# AMP_2_0_Single_Channel.net
KiCad netlist of a schematic drawn in EAGLE
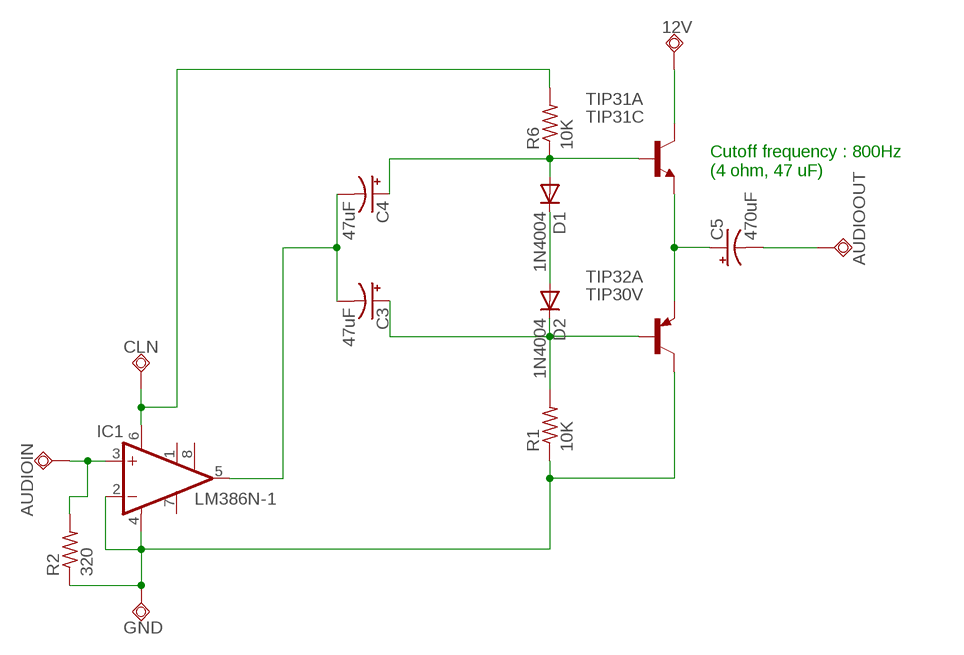
[diagram p0: schematic, sheet 1]

(export (version "E")
  (design (tool "Eeschema 10.0.6"))
  (components
    (comp (ref "12V")
      (value "TPSQPAD1-20")
      (footprint "eagle-import:P1-20")
      (libsource (lib "eagle-import") (part "TPSQPAD1-20"))
    )
    (comp (ref "AUDIOIN")
      (value "TPSQPAD1-20")
      (footprint "eagle-import:P1-20")
      (libsource (lib "eagle-import") (part "TPSQPAD1-20"))
    )
    (comp (ref "AUDIOOUT")
      (value "TPSQPAD1-20")
      (footprint "eagle-import:P1-20")
      (libsource (lib "eagle-import") (part "TPSQPAD1-20"))
    )
    (comp (ref "C3")
      (value "47uF")
      (footprint "eagle-import:E5-4")
      (libsource (lib "eagle-import") (part "CPOL-USE5-4"))
    )
    (comp (ref "C4")
      (value "47uF")
      (footprint "eagle-import:E5-4")
      (libsource (lib "eagle-import") (part "CPOL-USE5-4"))
    )
    (comp (ref "C5")
      (value "470uF")
      (footprint "eagle-import:E5-4")
      (libsource (lib "eagle-import") (part "CPOL-USE5-4"))
    )
    (comp (ref "CLN")
      (value "TPSQPAD1-20")
      (footprint "eagle-import:P1-20")
      (libsource (lib "eagle-import") (part "TPSQPAD1-20"))
    )
    (comp (ref "D1")
      (value "1N4004")
      (footprint "eagle-import:DO41-10")
      (libsource (lib "eagle-import") (part "1N4004"))
    )
    (comp (ref "D2")
      (value "1N4004")
      (footprint "eagle-import:DO41-10")
      (libsource (lib "eagle-import") (part "1N4004"))
    )
    (comp (ref "GND")
      (value "TPSQPAD1-20")
      (footprint "eagle-import:P1-20")
      (libsource (lib "eagle-import") (part "TPSQPAD1-20"))
    )
    (comp (ref "IC1")
      (value "LM386N-1")
      (footprint "eagle-import:DIL08")
      (libsource (lib "eagle-import") (part "LM386?-N1"))
    )
    (comp (ref "R1")
      (value "10K")
      (footprint "eagle-import:0204_7")
      (libsource (lib "eagle-import") (part "R-US_0204/7"))
    )
    (comp (ref "R2")
      (value "320")
      (footprint "eagle-import:0204_7")
      (libsource (lib "eagle-import") (part "R-US_0204/7"))
    )
    (comp (ref "R6")
      (value "10K")
      (footprint "eagle-import:0204_7")
      (libsource (lib "eagle-import") (part "R-US_0204/7"))
    )
    (comp (ref "TIP31A")
      (value "TIP31C")
      (footprint "eagle-import:TO220V")
      (libsource (lib "eagle-import") (part "TIP31C"))
    )
    (comp (ref "TIP32A")
      (value "TIP30V")
      (footprint "eagle-import:TO220V")
      (libsource (lib "eagle-import") (part "TIP30V"))
    )
  )
  (nets
    (net (code "1") (name "Net-(AUDIOOUT-PadTP)") (class "Default")
      (node (ref "AUDIOOUT") (pin "TP") (pinfunction "TP_TP") (pintype "input"))
      (node (ref "C5") (pin "-") (pinfunction "-_-") (pintype "passive"))
    )
    (net (code "2") (name "Net-(D1-PadC)") (class "Default")
      (node (ref "D1") (pin "C") (pinfunction "C_C") (pintype "passive"))
      (node (ref "D2") (pin "A") (pinfunction "A_A") (pintype "passive"))
    )
    (net (code "3") (name "Net-(IC1-+IN)") (class "Default")
      (node (ref "AUDIOIN") (pin "TP") (pinfunction "TP_TP") (pintype "input"))
      (node (ref "IC1") (pin "3") (pinfunction "+IN_3") (pintype "input"))
      (node (ref "R2") (pin "2") (pinfunction "2_2") (pintype "passive"))
    )
    (net (code "4") (name "Net-(IC1--IN)") (class "Default")
      (node (ref "GND") (pin "TP") (pinfunction "TP_TP") (pintype "input"))
      (node (ref "IC1") (pin "2") (pinfunction "-IN_2") (pintype "input"))
      (node (ref "IC1") (pin "4") (pinfunction "GND_4") (pintype "power_in"))
      (node (ref "R1") (pin "1") (pinfunction "1_1") (pintype "passive"))
      (node (ref "R2") (pin "1") (pinfunction "1_1") (pintype "passive"))
      (node (ref "TIP32A") (pin "2") (pinfunction "C_2") (pintype "passive"))
    )
    (net (code "5") (name "Net-(IC1-OUT)") (class "Default")
      (node (ref "C3") (pin "-") (pinfunction "-_-") (pintype "passive"))
      (node (ref "C4") (pin "-") (pinfunction "-_-") (pintype "passive"))
      (node (ref "IC1") (pin "5") (pinfunction "OUT_5") (pintype "output"))
    )
    (net (code "6") (name "Net-(IC1-VS)") (class "Default")
      (node (ref "CLN") (pin "TP") (pinfunction "TP_TP") (pintype "input"))
      (node (ref "IC1") (pin "6") (pinfunction "VS_6") (pintype "power_in"))
      (node (ref "R6") (pin "2") (pinfunction "2_2") (pintype "passive"))
    )
    (net (code "7") (name "Net-(TIP31A-B)") (class "Default")
      (node (ref "C4") (pin "+") (pinfunction "+_+") (pintype "passive"))
      (node (ref "D1") (pin "A") (pinfunction "A_A") (pintype "passive"))
      (node (ref "R6") (pin "1") (pinfunction "1_1") (pintype "passive"))
      (node (ref "TIP31A") (pin "1") (pinfunction "B_1") (pintype "passive"))
    )
    (net (code "8") (name "Net-(TIP31A-C)") (class "Default")
      (node (ref "12V") (pin "TP") (pinfunction "TP_TP") (pintype "input"))
      (node (ref "TIP31A") (pin "2") (pinfunction "C_2") (pintype "passive"))
    )
    (net (code "9") (name "Net-(TIP31A-E)") (class "Default")
      (node (ref "C5") (pin "+") (pinfunction "+_+") (pintype "passive"))
      (node (ref "TIP31A") (pin "3") (pinfunction "E_3") (pintype "passive"))
      (node (ref "TIP32A") (pin "3") (pinfunction "E_3") (pintype "passive"))
    )
    (net (code "10") (name "Net-(TIP32A-B)") (class "Default")
      (node (ref "C3") (pin "+") (pinfunction "+_+") (pintype "passive"))
      (node (ref "D2") (pin "C") (pinfunction "C_C") (pintype "passive"))
      (node (ref "R1") (pin "2") (pinfunction "2_2") (pintype "passive"))
      (node (ref "TIP32A") (pin "1") (pinfunction "B_1") (pintype "passive"))
    )
    (net (code "11") (name "unconnected-(IC1-BYPASS-Pad7)") (class "Default")
      (node (ref "IC1") (pin "7") (pinfunction "BYPASS_7") (pintype "passive"))
    )
    (net (code "12") (name "unconnected-(IC1-GAIN-Pad1)") (class "Default")
      (node (ref "IC1") (pin "1") (pinfunction "GAIN_1") (pintype "passive"))
    )
    (net (code "13") (name "unconnected-(IC1-GAIN-Pad8)") (class "Default")
      (node (ref "IC1") (pin "8") (pinfunction "GAIN_8") (pintype "passive"))
    )
  )
)
